# SD_Card.net
KiCad netlist of a schematic drawn in Altium Designer
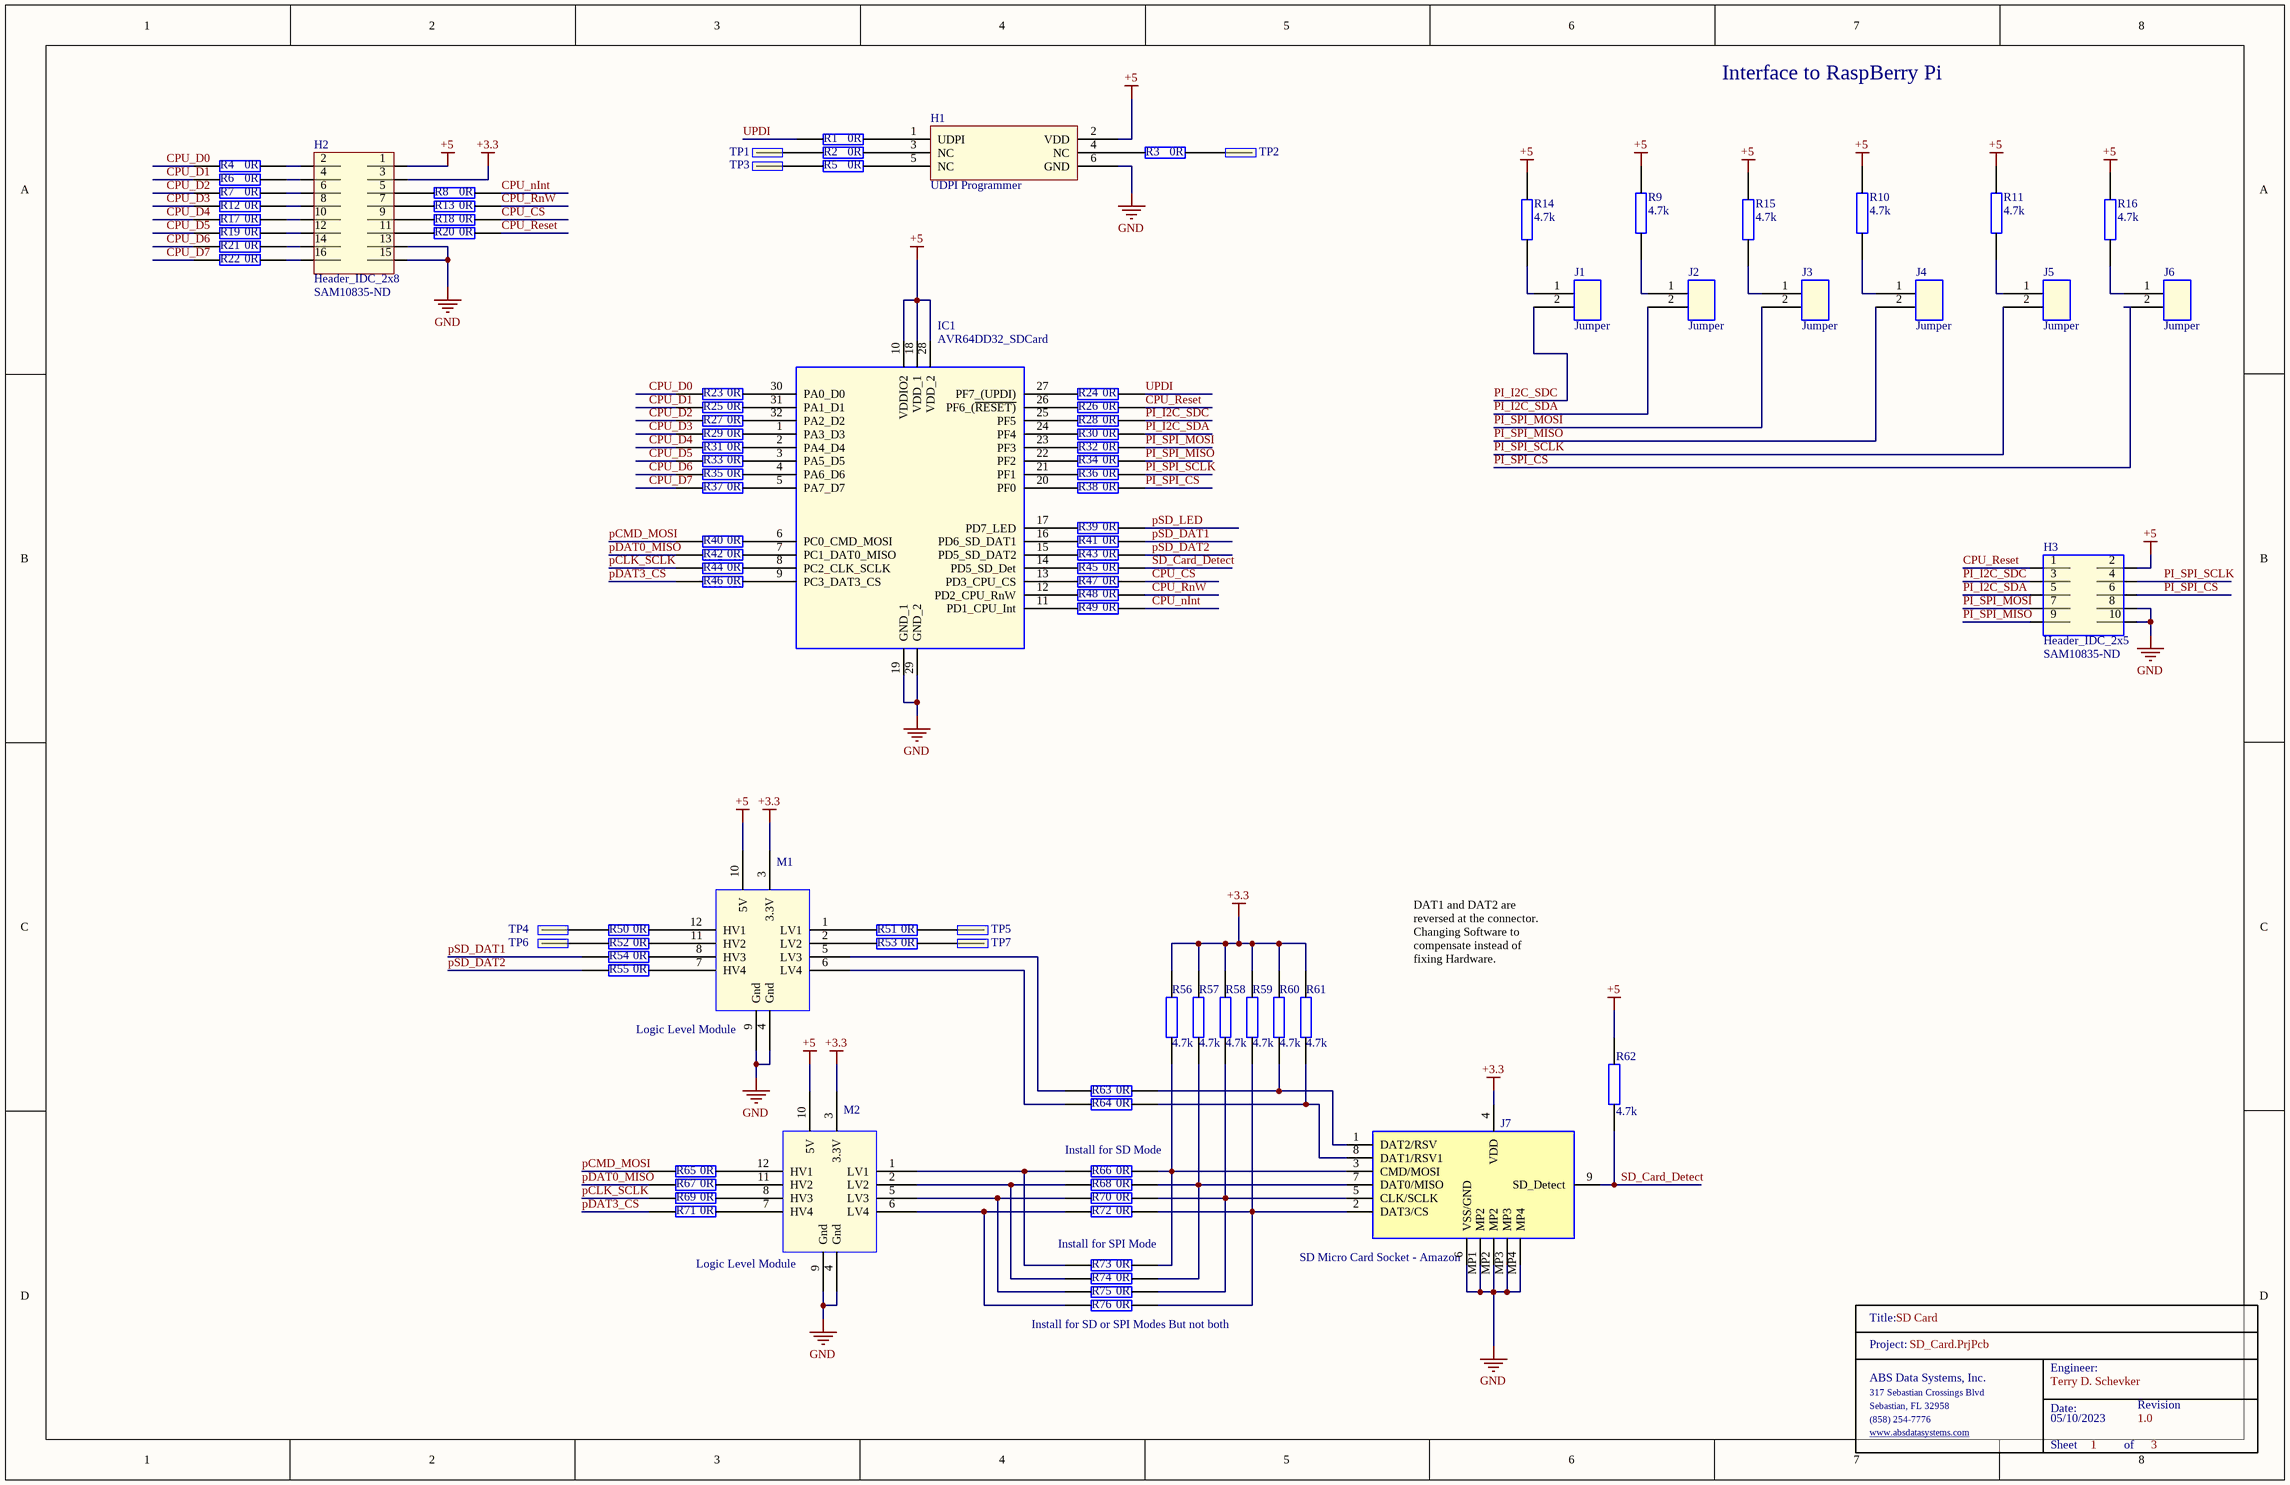
[diagram p0: SD_Card.SchDoc]

(export (version "E")
  (design (tool "Eeschema 10.0.6"))
  (components
    (comp (ref "H1")
      (value "UDPI Programmer")
      (footprint "HDR2X3")
      (description "6 Pin 2X3 Through Hole Header")
      (libsource (lib "Misc") (part "UDPI Programmer"))
    )
    (comp (ref "H2")
      (value "Header_IDC_2x8")
      (footprint "HEADER16")
      (description "16 Pin 2x8 Through Hold IDC Connector")
      (fields
        (field (name "MANUFACTURER") "Samtec")
        (field (name "MANUFACTURER PART NUMBER") "TST-108-01-G-D")
        (field (name "SUPPLIER PART NUMBER 1") "SAM10835-ND")
      )
      (libsource (lib "Misc") (part "Header_IDC_2x8"))
    )
    (comp (ref "H3")
      (value "Header_IDC_2x5")
      (footprint "HDR2X5")
      (description "10 Pin 2x5 Through Hold IDC Connector")
      (fields
        (field (name "MANUFACTURER") "Samtec")
        (field (name "MANUFACTURER PART NUMBER") "TST-105-01-G-D")
        (field (name "SUPPLIER PART NUMBER 1") "SAM10835-ND")
      )
      (libsource (lib "Misc") (part "Header_IDC_2x5"))
    )
    (comp (ref "IC1")
      (value "AVR64DD32_SDCard")
      (footprint "QFP80P900X900X120-32N")
      (description "Integrated Circuit")
      (fields (field (name "MANUFACTURER_PART_NUMBER") "AVR64DD32-I/PT ¦ MULTI-VOLTAGE I/O"))
      (libsource (lib "CPU_Memory") (part "AVR64DD32_SDCard"))
    )
    (comp (ref "J1")
      (value "Jumper")
      (footprint "Jumper")
      (description "16 Pin 3x8 Through Hold Jumprts")
      (fields
        (field (name "MANUFACTURER") "Samtec")
        (field (name "MANUFACTURER PART NUMBER") "TST-108-01-G-D")
      )
      (libsource (lib "Misc") (part "Jumper"))
    )
    (comp (ref "J2")
      (value "Jumper")
      (footprint "Jumper")
      (description "16 Pin 3x8 Through Hold Jumprts")
      (fields
        (field (name "MANUFACTURER") "Samtec")
        (field (name "MANUFACTURER PART NUMBER") "TST-108-01-G-D")
      )
      (libsource (lib "Misc") (part "Jumper"))
    )
    (comp (ref "J3")
      (value "Jumper")
      (footprint "Jumper")
      (description "16 Pin 3x8 Through Hold Jumprts")
      (fields
        (field (name "MANUFACTURER") "Samtec")
        (field (name "MANUFACTURER PART NUMBER") "TST-108-01-G-D")
      )
      (libsource (lib "Misc") (part "Jumper"))
    )
    (comp (ref "J4")
      (value "Jumper")
      (footprint "Jumper")
      (description "16 Pin 3x8 Through Hold Jumprts")
      (fields
        (field (name "MANUFACTURER") "Samtec")
        (field (name "MANUFACTURER PART NUMBER") "TST-108-01-G-D")
      )
      (libsource (lib "Misc") (part "Jumper"))
    )
    (comp (ref "J5")
      (value "Jumper")
      (footprint "Jumper")
      (description "16 Pin 3x8 Through Hold Jumprts")
      (fields
        (field (name "MANUFACTURER") "Samtec")
        (field (name "MANUFACTURER PART NUMBER") "TST-108-01-G-D")
      )
      (libsource (lib "Misc") (part "Jumper"))
    )
    (comp (ref "J6")
      (value "Jumper")
      (footprint "Jumper")
      (description "16 Pin 3x8 Through Hold Jumprts")
      (fields
        (field (name "MANUFACTURER") "Samtec")
        (field (name "MANUFACTURER PART NUMBER") "TST-108-01-G-D")
      )
      (libsource (lib "Misc") (part "Jumper"))
    )
    (comp (ref "J7")
      (value "SD Micro Card Socket - Amazon")
      (footprint "SDMicroConnector")
      (description "Memory Card Connectors 9P R/A SMT MICRO SD HINGE PUSH-PULL")
      (fields
        (field (name "MOUSER PART NUMBER") "798-DM3CSSF")
        (field (name "MANUFACTURER_PART_NUMBER") "DM3CS-SF")
      )
      (libsource (lib "Connectors") (part "SD_Micro_Socket"))
    )
    (comp (ref "M1")
      (value "Logic Level Module")
      (footprint "Logic_Level_Module")
      (description "Logic Level Converter Module")
      (libsource (lib "Logic") (part "Logic_Level_Module"))
    )
    (comp (ref "M2")
      (value "Logic Level Module")
      (footprint "Logic_Level_Module")
      (description "Logic Level Converter Module")
      (libsource (lib "Logic") (part "Logic_Level_Module"))
    )
    (comp (ref "R1")
      (value "0R")
      (footprint "0603")
      (description "YAGEO 0603 0 ohm")
      (fields
        (field (name "MOUSER PART NUMBER") "603-RC0603JR-070RL")
        (field (name "MANUFACTURER_PART_NUMBER") "RC0603JR-070RL")
      )
      (libsource (lib "Resistors") (part "RC0603JR-070RL"))
    )
    (comp (ref "R2")
      (value "0R")
      (footprint "0603")
      (description "YAGEO 0603 0 ohm")
      (fields
        (field (name "MOUSER PART NUMBER") "603-RC0603JR-070RL")
        (field (name "MANUFACTURER_PART_NUMBER") "RC0603JR-070RL")
      )
      (libsource (lib "Resistors") (part "RC0603JR-070RL"))
    )
    (comp (ref "R3")
      (value "0R")
      (footprint "0603")
      (description "YAGEO 0603 0 ohm")
      (fields
        (field (name "MOUSER PART NUMBER") "603-RC0603JR-070RL")
        (field (name "MANUFACTURER_PART_NUMBER") "RC0603JR-070RL")
      )
      (libsource (lib "Resistors") (part "RC0603JR-070RL"))
    )
    (comp (ref "R4")
      (value "0R")
      (footprint "0603")
      (description "YAGEO 0603 0 ohm")
      (fields
        (field (name "MOUSER PART NUMBER") "603-RC0603JR-070RL")
        (field (name "MANUFACTURER_PART_NUMBER") "RC0603JR-070RL")
      )
      (libsource (lib "Resistors") (part "RC0603JR-070RL"))
    )
    (comp (ref "R5")
      (value "0R")
      (footprint "0603")
      (description "YAGEO 0603 0 ohm")
      (fields
        (field (name "MOUSER PART NUMBER") "603-RC0603JR-070RL")
        (field (name "MANUFACTURER_PART_NUMBER") "RC0603JR-070RL")
      )
      (libsource (lib "Resistors") (part "RC0603JR-070RL"))
    )
    (comp (ref "R6")
      (value "0R")
      (footprint "0603")
      (description "YAGEO 0603 0 ohm")
      (fields
        (field (name "MOUSER PART NUMBER") "603-RC0603JR-070RL")
        (field (name "MANUFACTURER_PART_NUMBER") "RC0603JR-070RL")
      )
      (libsource (lib "Resistors") (part "RC0603JR-070RL"))
    )
    (comp (ref "R7")
      (value "0R")
      (footprint "0603")
      (description "YAGEO 0603 0 ohm")
      (fields
        (field (name "MOUSER PART NUMBER") "603-RC0603JR-070RL")
        (field (name "MANUFACTURER_PART_NUMBER") "RC0603JR-070RL")
      )
      (libsource (lib "Resistors") (part "RC0603JR-070RL"))
    )
    (comp (ref "R8")
      (value "0R")
      (footprint "0603")
      (description "YAGEO 0603 0 ohm")
      (fields
        (field (name "MOUSER PART NUMBER") "603-RC0603JR-070RL")
        (field (name "MANUFACTURER_PART_NUMBER") "RC0603JR-070RL")
      )
      (libsource (lib "Resistors") (part "RC0603JR-070RL"))
    )
    (comp (ref "R9")
      (value "4.7k")
      (footprint "0603")
      (description "YAGEO 0603 4.7k")
      (fields
        (field (name "MOUSER PART NUMBER") "603-RC0603JR-070RL")
        (field (name "MANUFACTURER_PART_NUMBER") "RC0603JR-070RL")
      )
      (libsource (lib "Resistors") (part "RC0603FR-104K7L"))
    )
    (comp (ref "R10")
      (value "4.7k")
      (footprint "0603")
      (description "YAGEO 0603 4.7k")
      (fields
        (field (name "MOUSER PART NUMBER") "603-RC0603JR-070RL")
        (field (name "MANUFACTURER_PART_NUMBER") "RC0603JR-070RL")
      )
      (libsource (lib "Resistors") (part "RC0603FR-104K7L"))
    )
    (comp (ref "R11")
      (value "4.7k")
      (footprint "0603")
      (description "YAGEO 0603 4.7k")
      (fields
        (field (name "MOUSER PART NUMBER") "603-RC0603JR-070RL")
        (field (name "MANUFACTURER_PART_NUMBER") "RC0603JR-070RL")
      )
      (libsource (lib "Resistors") (part "RC0603FR-104K7L"))
    )
    (comp (ref "R12")
      (value "0R")
      (footprint "0603")
      (description "YAGEO 0603 0 ohm")
      (fields
        (field (name "MOUSER PART NUMBER") "603-RC0603JR-070RL")
        (field (name "MANUFACTURER_PART_NUMBER") "RC0603JR-070RL")
      )
      (libsource (lib "Resistors") (part "RC0603JR-070RL"))
    )
    (comp (ref "R13")
      (value "0R")
      (footprint "0603")
      (description "YAGEO 0603 0 ohm")
      (fields
        (field (name "MOUSER PART NUMBER") "603-RC0603JR-070RL")
        (field (name "MANUFACTURER_PART_NUMBER") "RC0603JR-070RL")
      )
      (libsource (lib "Resistors") (part "RC0603JR-070RL"))
    )
    (comp (ref "R14")
      (value "4.7k")
      (footprint "0603")
      (description "YAGEO 0603 4.7k")
      (fields
        (field (name "MOUSER PART NUMBER") "603-RC0603JR-070RL")
        (field (name "MANUFACTURER_PART_NUMBER") "RC0603JR-070RL")
      )
      (libsource (lib "Resistors") (part "RC0603FR-104K7L"))
    )
    (comp (ref "R15")
      (value "4.7k")
      (footprint "0603")
      (description "YAGEO 0603 4.7k")
      (fields
        (field (name "MOUSER PART NUMBER") "603-RC0603JR-070RL")
        (field (name "MANUFACTURER_PART_NUMBER") "RC0603JR-070RL")
      )
      (libsource (lib "Resistors") (part "RC0603FR-104K7L"))
    )
    (comp (ref "R16")
      (value "4.7k")
      (footprint "0603")
      (description "YAGEO 0603 4.7k")
      (fields
        (field (name "MOUSER PART NUMBER") "603-RC0603JR-070RL")
        (field (name "MANUFACTURER_PART_NUMBER") "RC0603JR-070RL")
      )
      (libsource (lib "Resistors") (part "RC0603FR-104K7L"))
    )
    (comp (ref "R17")
      (value "0R")
      (footprint "0603")
      (description "YAGEO 0603 0 ohm")
      (fields
        (field (name "MOUSER PART NUMBER") "603-RC0603JR-070RL")
        (field (name "MANUFACTURER_PART_NUMBER") "RC0603JR-070RL")
      )
      (libsource (lib "Resistors") (part "RC0603JR-070RL"))
    )
    (comp (ref "R18")
      (value "0R")
      (footprint "0603")
      (description "YAGEO 0603 0 ohm")
      (fields
        (field (name "MOUSER PART NUMBER") "603-RC0603JR-070RL")
        (field (name "MANUFACTURER_PART_NUMBER") "RC0603JR-070RL")
      )
      (libsource (lib "Resistors") (part "RC0603JR-070RL"))
    )
    (comp (ref "R19")
      (value "0R")
      (footprint "0603")
      (description "YAGEO 0603 0 ohm")
      (fields
        (field (name "MOUSER PART NUMBER") "603-RC0603JR-070RL")
        (field (name "MANUFACTURER_PART_NUMBER") "RC0603JR-070RL")
      )
      (libsource (lib "Resistors") (part "RC0603JR-070RL"))
    )
    (comp (ref "R20")
      (value "0R")
      (footprint "0603")
      (description "YAGEO 0603 0 ohm")
      (fields
        (field (name "MOUSER PART NUMBER") "603-RC0603JR-070RL")
        (field (name "MANUFACTURER_PART_NUMBER") "RC0603JR-070RL")
      )
      (libsource (lib "Resistors") (part "RC0603JR-070RL"))
    )
    (comp (ref "R21")
      (value "0R")
      (footprint "0603")
      (description "YAGEO 0603 0 ohm")
      (fields
        (field (name "MOUSER PART NUMBER") "603-RC0603JR-070RL")
        (field (name "MANUFACTURER_PART_NUMBER") "RC0603JR-070RL")
      )
      (libsource (lib "Resistors") (part "RC0603JR-070RL"))
    )
    (comp (ref "R22")
      (value "0R")
      (footprint "0603")
      (description "YAGEO 0603 0 ohm")
      (fields
        (field (name "MOUSER PART NUMBER") "603-RC0603JR-070RL")
        (field (name "MANUFACTURER_PART_NUMBER") "RC0603JR-070RL")
      )
      (libsource (lib "Resistors") (part "RC0603JR-070RL"))
    )
    (comp (ref "R23")
      (value "0R")
      (footprint "0603")
      (description "YAGEO 0603 0 ohm")
      (fields
        (field (name "MOUSER PART NUMBER") "603-RC0603JR-070RL")
        (field (name "MANUFACTURER_PART_NUMBER") "RC0603JR-070RL")
      )
      (libsource (lib "Resistors") (part "RC0603JR-070RL"))
    )
    (comp (ref "R24")
      (value "0R")
      (footprint "0603")
      (description "YAGEO 0603 0 ohm")
      (fields
        (field (name "MOUSER PART NUMBER") "603-RC0603JR-070RL")
        (field (name "MANUFACTURER_PART_NUMBER") "RC0603JR-070RL")
      )
      (libsource (lib "Resistors") (part "RC0603JR-070RL"))
    )
    (comp (ref "R25")
      (value "0R")
      (footprint "0603")
      (description "YAGEO 0603 0 ohm")
      (fields
        (field (name "MOUSER PART NUMBER") "603-RC0603JR-070RL")
        (field (name "MANUFACTURER_PART_NUMBER") "RC0603JR-070RL")
      )
      (libsource (lib "Resistors") (part "RC0603JR-070RL"))
    )
    (comp (ref "R26")
      (value "0R")
      (footprint "0603")
      (description "YAGEO 0603 0 ohm")
      (fields
        (field (name "MOUSER PART NUMBER") "603-RC0603JR-070RL")
        (field (name "MANUFACTURER_PART_NUMBER") "RC0603JR-070RL")
      )
      (libsource (lib "Resistors") (part "RC0603JR-070RL"))
    )
    (comp (ref "R27")
      (value "0R")
      (footprint "0603")
      (description "YAGEO 0603 0 ohm")
      (fields
        (field (name "MOUSER PART NUMBER") "603-RC0603JR-070RL")
        (field (name "MANUFACTURER_PART_NUMBER") "RC0603JR-070RL")
      )
      (libsource (lib "Resistors") (part "RC0603JR-070RL"))
    )
    (comp (ref "R28")
      (value "0R")
      (footprint "0603")
      (description "YAGEO 0603 0 ohm")
      (fields
        (field (name "MOUSER PART NUMBER") "603-RC0603JR-070RL")
        (field (name "MANUFACTURER_PART_NUMBER") "RC0603JR-070RL")
      )
      (libsource (lib "Resistors") (part "RC0603JR-070RL"))
    )
    (comp (ref "R29")
      (value "0R")
      (footprint "0603")
      (description "YAGEO 0603 0 ohm")
      (fields
        (field (name "MOUSER PART NUMBER") "603-RC0603JR-070RL")
        (field (name "MANUFACTURER_PART_NUMBER") "RC0603JR-070RL")
      )
      (libsource (lib "Resistors") (part "RC0603JR-070RL"))
    )
    (comp (ref "R30")
      (value "0R")
      (footprint "0603")
      (description "YAGEO 0603 0 ohm")
      (fields
        (field (name "MOUSER PART NUMBER") "603-RC0603JR-070RL")
        (field (name "MANUFACTURER_PART_NUMBER") "RC0603JR-070RL")
      )
      (libsource (lib "Resistors") (part "RC0603JR-070RL"))
    )
    (comp (ref "R31")
      (value "0R")
      (footprint "0603")
      (description "YAGEO 0603 0 ohm")
      (fields
        (field (name "MOUSER PART NUMBER") "603-RC0603JR-070RL")
        (field (name "MANUFACTURER_PART_NUMBER") "RC0603JR-070RL")
      )
      (libsource (lib "Resistors") (part "RC0603JR-070RL"))
    )
    (comp (ref "R32")
      (value "0R")
      (footprint "0603")
      (description "YAGEO 0603 0 ohm")
      (fields
        (field (name "MOUSER PART NUMBER") "603-RC0603JR-070RL")
        (field (name "MANUFACTURER_PART_NUMBER") "RC0603JR-070RL")
      )
      (libsource (lib "Resistors") (part "RC0603JR-070RL"))
    )
    (comp (ref "R33")
      (value "0R")
      (footprint "0603")
      (description "YAGEO 0603 0 ohm")
      (fields
        (field (name "MOUSER PART NUMBER") "603-RC0603JR-070RL")
        (field (name "MANUFACTURER_PART_NUMBER") "RC0603JR-070RL")
      )
      (libsource (lib "Resistors") (part "RC0603JR-070RL"))
    )
    (comp (ref "R34")
      (value "0R")
      (footprint "0603")
      (description "YAGEO 0603 0 ohm")
      (fields
        (field (name "MOUSER PART NUMBER") "603-RC0603JR-070RL")
        (field (name "MANUFACTURER_PART_NUMBER") "RC0603JR-070RL")
      )
      (libsource (lib "Resistors") (part "RC0603JR-070RL"))
    )
    (comp (ref "R35")
      (value "0R")
      (footprint "0603")
      (description "YAGEO 0603 0 ohm")
      (fields
        (field (name "MOUSER PART NUMBER") "603-RC0603JR-070RL")
        (field (name "MANUFACTURER_PART_NUMBER") "RC0603JR-070RL")
      )
      (libsource (lib "Resistors") (part "RC0603JR-070RL"))
    )
    (comp (ref "R36")
      (value "0R")
      (footprint "0603")
      (description "YAGEO 0603 0 ohm")
      (fields
        (field (name "MOUSER PART NUMBER") "603-RC0603JR-070RL")
        (field (name "MANUFACTURER_PART_NUMBER") "RC0603JR-070RL")
      )
      (libsource (lib "Resistors") (part "RC0603JR-070RL"))
    )
    (comp (ref "R37")
      (value "0R")
      (footprint "0603")
      (description "YAGEO 0603 0 ohm")
      (fields
        (field (name "MOUSER PART NUMBER") "603-RC0603JR-070RL")
        (field (name "MANUFACTURER_PART_NUMBER") "RC0603JR-070RL")
      )
      (libsource (lib "Resistors") (part "RC0603JR-070RL"))
    )
    (comp (ref "R38")
      (value "0R")
      (footprint "0603")
      (description "YAGEO 0603 0 ohm")
      (fields
        (field (name "MOUSER PART NUMBER") "603-RC0603JR-070RL")
        (field (name "MANUFACTURER_PART_NUMBER") "RC0603JR-070RL")
      )
      (libsource (lib "Resistors") (part "RC0603JR-070RL"))
    )
    (comp (ref "R39")
      (value "0R")
      (footprint "0603")
      (description "YAGEO 0603 0 ohm")
      (fields
        (field (name "MOUSER PART NUMBER") "603-RC0603JR-070RL")
        (field (name "MANUFACTURER_PART_NUMBER") "RC0603JR-070RL")
      )
      (libsource (lib "Resistors") (part "RC0603JR-070RL"))
    )
    (comp (ref "R40")
      (value "0R")
      (footprint "0603")
      (description "YAGEO 0603 0 ohm")
      (fields
        (field (name "MOUSER PART NUMBER") "603-RC0603JR-070RL")
        (field (name "MANUFACTURER_PART_NUMBER") "RC0603JR-070RL")
      )
      (libsource (lib "Resistors") (part "RC0603JR-070RL"))
    )
    (comp (ref "R41")
      (value "0R")
      (footprint "0603")
      (description "YAGEO 0603 0 ohm")
      (fields
        (field (name "MOUSER PART NUMBER") "603-RC0603JR-070RL")
        (field (name "MANUFACTURER_PART_NUMBER") "RC0603JR-070RL")
      )
      (libsource (lib "Resistors") (part "RC0603JR-070RL"))
    )
    (comp (ref "R42")
      (value "0R")
      (footprint "0603")
      (description "YAGEO 0603 0 ohm")
      (fields
        (field (name "MOUSER PART NUMBER") "603-RC0603JR-070RL")
        (field (name "MANUFACTURER_PART_NUMBER") "RC0603JR-070RL")
      )
      (libsource (lib "Resistors") (part "RC0603JR-070RL"))
    )
    (comp (ref "R43")
      (value "0R")
      (footprint "0603")
      (description "YAGEO 0603 0 ohm")
      (fields
        (field (name "MOUSER PART NUMBER") "603-RC0603JR-070RL")
        (field (name "MANUFACTURER_PART_NUMBER") "RC0603JR-070RL")
      )
      (libsource (lib "Resistors") (part "RC0603JR-070RL"))
    )
    (comp (ref "R44")
      (value "0R")
      (footprint "0603")
      (description "YAGEO 0603 0 ohm")
      (fields
        (field (name "MOUSER PART NUMBER") "603-RC0603JR-070RL")
        (field (name "MANUFACTURER_PART_NUMBER") "RC0603JR-070RL")
      )
      (libsource (lib "Resistors") (part "RC0603JR-070RL"))
    )
    (comp (ref "R45")
      (value "0R")
      (footprint "0603")
      (description "YAGEO 0603 0 ohm")
      (fields
        (field (name "MOUSER PART NUMBER") "603-RC0603JR-070RL")
        (field (name "MANUFACTURER_PART_NUMBER") "RC0603JR-070RL")
      )
      (libsource (lib "Resistors") (part "RC0603JR-070RL"))
    )
    (comp (ref "R46")
      (value "0R")
      (footprint "0603")
      (description "YAGEO 0603 0 ohm")
      (fields
        (field (name "MOUSER PART NUMBER") "603-RC0603JR-070RL")
        (field (name "MANUFACTURER_PART_NUMBER") "RC0603JR-070RL")
      )
      (libsource (lib "Resistors") (part "RC0603JR-070RL"))
    )
    (comp (ref "R47")
      (value "0R")
      (footprint "0603")
      (description "YAGEO 0603 0 ohm")
      (fields
        (field (name "MOUSER PART NUMBER") "603-RC0603JR-070RL")
        (field (name "MANUFACTURER_PART_NUMBER") "RC0603JR-070RL")
      )
      (libsource (lib "Resistors") (part "RC0603JR-070RL"))
    )
    (comp (ref "R48")
      (value "0R")
      (footprint "0603")
      (description "YAGEO 0603 0 ohm")
      (fields
        (field (name "MOUSER PART NUMBER") "603-RC0603JR-070RL")
        (field (name "MANUFACTURER_PART_NUMBER") "RC0603JR-070RL")
      )
      (libsource (lib "Resistors") (part "RC0603JR-070RL"))
    )
    (comp (ref "R49")
      (value "0R")
      (footprint "0603")
      (description "YAGEO 0603 0 ohm")
      (fields
        (field (name "MOUSER PART NUMBER") "603-RC0603JR-070RL")
        (field (name "MANUFACTURER_PART_NUMBER") "RC0603JR-070RL")
      )
      (libsource (lib "Resistors") (part "RC0603JR-070RL"))
    )
    (comp (ref "R50")
      (value "0R")
      (footprint "0603")
      (description "YAGEO 0603 0 ohm")
      (fields
        (field (name "MOUSER PART NUMBER") "603-RC0603JR-070RL")
        (field (name "MANUFACTURER_PART_NUMBER") "RC0603JR-070RL")
      )
      (libsource (lib "Resistors") (part "RC0603JR-070RL"))
    )
    (comp (ref "R51")
      (value "0R")
      (footprint "0603")
      (description "YAGEO 0603 0 ohm")
      (fields
        (field (name "MOUSER PART NUMBER") "603-RC0603JR-070RL")
        (field (name "MANUFACTURER_PART_NUMBER") "RC0603JR-070RL")
      )
      (libsource (lib "Resistors") (part "RC0603JR-070RL"))
    )
    (comp (ref "R52")
      (value "0R")
      (footprint "0603")
      (description "YAGEO 0603 0 ohm")
      (fields
        (field (name "MOUSER PART NUMBER") "603-RC0603JR-070RL")
        (field (name "MANUFACTURER_PART_NUMBER") "RC0603JR-070RL")
      )
      (libsource (lib "Resistors") (part "RC0603JR-070RL"))
    )
    (comp (ref "R53")
      (value "0R")
      (footprint "0603")
      (description "YAGEO 0603 0 ohm")
      (fields
        (field (name "MOUSER PART NUMBER") "603-RC0603JR-070RL")
        (field (name "MANUFACTURER_PART_NUMBER") "RC0603JR-070RL")
      )
      (libsource (lib "Resistors") (part "RC0603JR-070RL"))
    )
    (comp (ref "R54")
      (value "0R")
      (footprint "0603")
      (description "YAGEO 0603 0 ohm")
      (fields
        (field (name "MOUSER PART NUMBER") "603-RC0603JR-070RL")
        (field (name "MANUFACTURER_PART_NUMBER") "RC0603JR-070RL")
      )
      (libsource (lib "Resistors") (part "RC0603JR-070RL"))
    )
    (comp (ref "R55")
      (value "0R")
      (footprint "0603")
      (description "YAGEO 0603 0 ohm")
      (fields
        (field (name "MOUSER PART NUMBER") "603-RC0603JR-070RL")
        (field (name "MANUFACTURER_PART_NUMBER") "RC0603JR-070RL")
      )
      (libsource (lib "Resistors") (part "RC0603JR-070RL"))
    )
    (comp (ref "R56")
      (value "4.7k")
      (footprint "0603")
      (description "YAGEO 0603 4.7k")
      (fields
        (field (name "MOUSER PART NUMBER") "603-RC0603JR-070RL")
        (field (name "MANUFACTURER_PART_NUMBER") "RC0603JR-070RL")
      )
      (libsource (lib "Resistors") (part "RC0603FR-104K7L"))
    )
    (comp (ref "R57")
      (value "4.7k")
      (footprint "0603")
      (description "YAGEO 0603 4.7k")
      (fields
        (field (name "MOUSER PART NUMBER") "603-RC0603JR-070RL")
        (field (name "MANUFACTURER_PART_NUMBER") "RC0603JR-070RL")
      )
      (libsource (lib "Resistors") (part "RC0603FR-104K7L"))
    )
    (comp (ref "R58")
      (value "4.7k")
      (footprint "0603")
      (description "YAGEO 0603 4.7k")
      (fields
        (field (name "MOUSER PART NUMBER") "603-RC0603JR-070RL")
        (field (name "MANUFACTURER_PART_NUMBER") "RC0603JR-070RL")
      )
      (libsource (lib "Resistors") (part "RC0603FR-104K7L"))
    )
    (comp (ref "R59")
      (value "4.7k")
      (footprint "0603")
      (description "YAGEO 0603 4.7k")
      (fields
        (field (name "MOUSER PART NUMBER") "603-RC0603JR-070RL")
        (field (name "MANUFACTURER_PART_NUMBER") "RC0603JR-070RL")
      )
      (libsource (lib "Resistors") (part "RC0603FR-104K7L"))
    )
    (comp (ref "R60")
      (value "4.7k")
      (footprint "0603")
      (description "YAGEO 0603 4.7k")
      (fields
        (field (name "MOUSER PART NUMBER") "603-RC0603JR-070RL")
        (field (name "MANUFACTURER_PART_NUMBER") "RC0603JR-070RL")
      )
      (libsource (lib "Resistors") (part "RC0603FR-104K7L"))
    )
    (comp (ref "R61")
      (value "4.7k")
      (footprint "0603")
      (description "YAGEO 0603 4.7k")
      (fields
        (field (name "MOUSER PART NUMBER") "603-RC0603JR-070RL")
        (field (name "MANUFACTURER_PART_NUMBER") "RC0603JR-070RL")
      )
      (libsource (lib "Resistors") (part "RC0603FR-104K7L"))
    )
    (comp (ref "R62")
      (value "4.7k")
      (footprint "0603")
      (description "YAGEO 0603 4.7k")
      (fields
        (field (name "MOUSER PART NUMBER") "603-RC0603JR-070RL")
        (field (name "MANUFACTURER_PART_NUMBER") "RC0603JR-070RL")
      )
      (libsource (lib "Resistors") (part "RC0603FR-104K7L"))
    )
    (comp (ref "R63")
      (value "0R")
      (footprint "0603")
      (description "YAGEO 0603 0 ohm")
      (fields
        (field (name "MOUSER PART NUMBER") "603-RC0603JR-070RL")
        (field (name "MANUFACTURER_PART_NUMBER") "RC0603JR-070RL")
      )
      (libsource (lib "Resistors") (part "RC0603JR-070RL"))
    )
    (comp (ref "R64")
      (value "0R")
      (footprint "0603")
      (description "YAGEO 0603 0 ohm")
      (fields
        (field (name "MOUSER PART NUMBER") "603-RC0603JR-070RL")
        (field (name "MANUFACTURER_PART_NUMBER") "RC0603JR-070RL")
      )
      (libsource (lib "Resistors") (part "RC0603JR-070RL"))
    )
    (comp (ref "R65")
      (value "0R")
      (footprint "0603")
      (description "YAGEO 0603 0 ohm")
      (fields
        (field (name "MOUSER PART NUMBER") "603-RC0603JR-070RL")
        (field (name "MANUFACTURER_PART_NUMBER") "RC0603JR-070RL")
      )
      (libsource (lib "Resistors") (part "RC0603JR-070RL"))
    )
    (comp (ref "R66")
      (value "0R")
      (footprint "0603")
      (description "YAGEO 0603 0 ohm")
      (fields
        (field (name "MOUSER PART NUMBER") "603-RC0603JR-070RL")
        (field (name "MANUFACTURER_PART_NUMBER") "RC0603JR-070RL")
      )
      (libsource (lib "Resistors") (part "RC0603JR-070RL"))
    )
    (comp (ref "R67")
      (value "0R")
      (footprint "0603")
      (description "YAGEO 0603 0 ohm")
      (fields
        (field (name "MOUSER PART NUMBER") "603-RC0603JR-070RL")
        (field (name "MANUFACTURER_PART_NUMBER") "RC0603JR-070RL")
      )
      (libsource (lib "Resistors") (part "RC0603JR-070RL"))
    )
    (comp (ref "R68")
      (value "0R")
      (footprint "0603")
      (description "YAGEO 0603 0 ohm")
      (fields
        (field (name "MOUSER PART NUMBER") "603-RC0603JR-070RL")
        (field (name "MANUFACTURER_PART_NUMBER") "RC0603JR-070RL")
      )
      (libsource (lib "Resistors") (part "RC0603JR-070RL"))
    )
    (comp (ref "R69")
      (value "0R")
      (footprint "0603")
      (description "YAGEO 0603 0 ohm")
      (fields
        (field (name "MOUSER PART NUMBER") "603-RC0603JR-070RL")
        (field (name "MANUFACTURER_PART_NUMBER") "RC0603JR-070RL")
      )
      (libsource (lib "Resistors") (part "RC0603JR-070RL"))
    )
    (comp (ref "R70")
      (value "0R")
      (footprint "0603")
      (description "YAGEO 0603 0 ohm")
      (fields
        (field (name "MOUSER PART NUMBER") "603-RC0603JR-070RL")
        (field (name "MANUFACTURER_PART_NUMBER") "RC0603JR-070RL")
      )
      (libsource (lib "Resistors") (part "RC0603JR-070RL"))
    )
    (comp (ref "R71")
      (value "0R")
      (footprint "0603")
      (description "YAGEO 0603 0 ohm")
      (fields
        (field (name "MOUSER PART NUMBER") "603-RC0603JR-070RL")
        (field (name "MANUFACTURER_PART_NUMBER") "RC0603JR-070RL")
      )
      (libsource (lib "Resistors") (part "RC0603JR-070RL"))
    )
    (comp (ref "R72")
      (value "0R")
      (footprint "0603")
      (description "YAGEO 0603 0 ohm")
      (fields
        (field (name "MOUSER PART NUMBER") "603-RC0603JR-070RL")
        (field (name "MANUFACTURER_PART_NUMBER") "RC0603JR-070RL")
      )
      (libsource (lib "Resistors") (part "RC0603JR-070RL"))
    )
    (comp (ref "R73")
      (value "0R")
      (footprint "0603")
      (description "YAGEO 0603 0 ohm")
      (fields
        (field (name "MOUSER PART NUMBER") "603-RC0603JR-070RL")
        (field (name "MANUFACTURER_PART_NUMBER") "RC0603JR-070RL")
      )
      (libsource (lib "Resistors") (part "RC0603JR-070RL"))
    )
    (comp (ref "R74")
      (value "0R")
      (footprint "0603")
      (description "YAGEO 0603 0 ohm")
      (fields
        (field (name "MOUSER PART NUMBER") "603-RC0603JR-070RL")
        (field (name "MANUFACTURER_PART_NUMBER") "RC0603JR-070RL")
      )
      (libsource (lib "Resistors") (part "RC0603JR-070RL"))
    )
    (comp (ref "R75")
      (value "0R")
      (footprint "0603")
      (description "YAGEO 0603 0 ohm")
      (fields
        (field (name "MOUSER PART NUMBER") "603-RC0603JR-070RL")
        (field (name "MANUFACTURER_PART_NUMBER") "RC0603JR-070RL")
      )
      (libsource (lib "Resistors") (part "RC0603JR-070RL"))
    )
    (comp (ref "R76")
      (value "0R")
      (footprint "0603")
      (description "YAGEO 0603 0 ohm")
      (fields
        (field (name "MOUSER PART NUMBER") "603-RC0603JR-070RL")
        (field (name "MANUFACTURER_PART_NUMBER") "RC0603JR-070RL")
      )
      (libsource (lib "Resistors") (part "RC0603JR-070RL"))
    )
    (comp (ref "TitleBlock_1") (value "TitleBlock") (libsource (lib "Misc") (part "TitleBlock")))
    (comp (ref "TP1")
      (value "TP")
      (footprint "TP")
      (fields
        (field (name "MANUFACTURER") "Samtec")
        (field (name "MANUFACTURER PART NUMBER") "TST-105-01-G-D")
      )
      (libsource (lib "") (part "TP_1"))
    )
    (comp (ref "TP2")
      (value "TP")
      (footprint "TP")
      (fields
        (field (name "MANUFACTURER") "Samtec")
        (field (name "MANUFACTURER PART NUMBER") "TST-105-01-G-D")
      )
      (libsource (lib "Misc") (part "TP"))
    )
    (comp (ref "TP3")
      (value "TP")
      (footprint "TP")
      (fields
        (field (name "MANUFACTURER") "Samtec")
        (field (name "MANUFACTURER PART NUMBER") "TST-105-01-G-D")
      )
      (libsource (lib "") (part "TP_1"))
    )
    (comp (ref "TP4")
      (value "TP")
      (footprint "TP")
      (fields
        (field (name "MANUFACTURER") "Samtec")
        (field (name "MANUFACTURER PART NUMBER") "TST-105-01-G-D")
      )
      (libsource (lib "") (part "TP_1"))
    )
    (comp (ref "TP5")
      (value "TP")
      (footprint "TP")
      (fields
        (field (name "MANUFACTURER") "Samtec")
        (field (name "MANUFACTURER PART NUMBER") "TST-105-01-G-D")
      )
      (libsource (lib "Misc") (part "TP"))
    )
    (comp (ref "TP6")
      (value "TP")
      (footprint "TP")
      (fields
        (field (name "MANUFACTURER") "Samtec")
        (field (name "MANUFACTURER PART NUMBER") "TST-105-01-G-D")
      )
      (libsource (lib "") (part "TP_1"))
    )
    (comp (ref "TP7")
      (value "TP")
      (footprint "TP")
      (fields
        (field (name "MANUFACTURER") "Samtec")
        (field (name "MANUFACTURER PART NUMBER") "TST-105-01-G-D")
      )
      (libsource (lib "Misc") (part "TP"))
    )
  )
  (nets
    (net (code "1") (name "+3.3") (class "Default")
      (node (ref "H2") (pin "3") (pinfunction "3_3") (pintype "passive"))
      (node (ref "J7") (pin "4") (pinfunction "VDD_4") (pintype "passive"))
      (node (ref "M1") (pin "3") (pinfunction "3.3V_3") (pintype "passive"))
      (node (ref "M2") (pin "3") (pinfunction "3.3V_3") (pintype "passive"))
      (node (ref "R56") (pin "2") (pinfunction "2_2") (pintype "passive"))
      (node (ref "R57") (pin "2") (pinfunction "2_2") (pintype "passive"))
      (node (ref "R58") (pin "2") (pinfunction "2_2") (pintype "passive"))
      (node (ref "R59") (pin "2") (pinfunction "2_2") (pintype "passive"))
      (node (ref "R60") (pin "2") (pinfunction "2_2") (pintype "passive"))
      (node (ref "R61") (pin "2") (pinfunction "2_2") (pintype "passive"))
    )
    (net (code "2") (name "+5") (class "Default")
      (node (ref "H1") (pin "2") (pinfunction "VDD_2") (pintype "passive"))
      (node (ref "H2") (pin "1") (pinfunction "1_1") (pintype "passive"))
      (node (ref "H3") (pin "2") (pinfunction "2_2") (pintype "passive"))
      (node (ref "IC1") (pin "10") (pinfunction "VDDIO2_10") (pintype "passive"))
      (node (ref "IC1") (pin "18") (pinfunction "VDD_1_18") (pintype "passive"))
      (node (ref "IC1") (pin "28") (pinfunction "VDD_2_28") (pintype "passive"))
      (node (ref "M1") (pin "10") (pinfunction "5V_10") (pintype "passive"))
      (node (ref "M2") (pin "10") (pinfunction "5V_10") (pintype "passive"))
      (node (ref "R10") (pin "2") (pinfunction "2_2") (pintype "passive"))
      (node (ref "R11") (pin "2") (pinfunction "2_2") (pintype "passive"))
      (node (ref "R14") (pin "2") (pinfunction "2_2") (pintype "passive"))
      (node (ref "R15") (pin "2") (pinfunction "2_2") (pintype "passive"))
      (node (ref "R16") (pin "1") (pinfunction "1_1") (pintype "passive"))
      (node (ref "R62") (pin "2") (pinfunction "2_2") (pintype "passive"))
      (node (ref "R9") (pin "2") (pinfunction "2_2") (pintype "passive"))
    )
    (net (code "3") (name "/CPU_CS") (class "Default")
      (node (ref "R18") (pin "2") (pinfunction "2_2") (pintype "passive"))
      (node (ref "R47") (pin "2") (pinfunction "2_2") (pintype "passive"))
    )
    (net (code "4") (name "/CPU_D0") (class "Default")
      (node (ref "R23") (pin "1") (pinfunction "1_1") (pintype "passive"))
      (node (ref "R4") (pin "1") (pinfunction "1_1") (pintype "passive"))
    )
    (net (code "5") (name "/CPU_D1") (class "Default")
      (node (ref "R25") (pin "1") (pinfunction "1_1") (pintype "passive"))
      (node (ref "R6") (pin "1") (pinfunction "1_1") (pintype "passive"))
    )
    (net (code "6") (name "/CPU_D2") (class "Default")
      (node (ref "R27") (pin "1") (pinfunction "1_1") (pintype "passive"))
      (node (ref "R7") (pin "1") (pinfunction "1_1") (pintype "passive"))
    )
    (net (code "7") (name "/CPU_D3") (class "Default")
      (node (ref "R12") (pin "1") (pinfunction "1_1") (pintype "passive"))
      (node (ref "R29") (pin "1") (pinfunction "1_1") (pintype "passive"))
    )
    (net (code "8") (name "/CPU_D4") (class "Default")
      (node (ref "R17") (pin "1") (pinfunction "1_1") (pintype "passive"))
      (node (ref "R31") (pin "1") (pinfunction "1_1") (pintype "passive"))
    )
    (net (code "9") (name "/CPU_D5") (class "Default")
      (node (ref "R19") (pin "1") (pinfunction "1_1") (pintype "passive"))
      (node (ref "R33") (pin "1") (pinfunction "1_1") (pintype "passive"))
    )
    (net (code "10") (name "/CPU_D6") (class "Default")
      (node (ref "R21") (pin "1") (pinfunction "1_1") (pintype "passive"))
      (node (ref "R35") (pin "1") (pinfunction "1_1") (pintype "passive"))
    )
    (net (code "11") (name "/CPU_D7") (class "Default")
      (node (ref "R22") (pin "1") (pinfunction "1_1") (pintype "passive"))
      (node (ref "R37") (pin "1") (pinfunction "1_1") (pintype "passive"))
    )
    (net (code "12") (name "/CPU_Reset") (class "Default")
      (node (ref "H3") (pin "1") (pinfunction "1_1") (pintype "passive"))
      (node (ref "R20") (pin "2") (pinfunction "2_2") (pintype "passive"))
      (node (ref "R26") (pin "2") (pinfunction "2_2") (pintype "passive"))
    )
    (net (code "13") (name "/CPU_RnW") (class "Default")
      (node (ref "R13") (pin "2") (pinfunction "2_2") (pintype "passive"))
      (node (ref "R48") (pin "2") (pinfunction "2_2") (pintype "passive"))
    )
    (net (code "14") (name "/CPU_nInt") (class "Default")
      (node (ref "R49") (pin "2") (pinfunction "2_2") (pintype "passive"))
      (node (ref "R8") (pin "2") (pinfunction "2_2") (pintype "passive"))
    )
    (net (code "15") (name "/PI_I2C_SDA") (class "Default")
      (node (ref "H3") (pin "5") (pinfunction "5_5") (pintype "passive"))
      (node (ref "J2") (pin "2") (pinfunction "2_2") (pintype "passive"))
      (node (ref "R30") (pin "2") (pinfunction "2_2") (pintype "passive"))
    )
    (net (code "16") (name "/PI_I2C_SDC") (class "Default")
      (node (ref "H3") (pin "3") (pinfunction "3_3") (pintype "passive"))
      (node (ref "J1") (pin "2") (pinfunction "2_2") (pintype "passive"))
      (node (ref "R28") (pin "2") (pinfunction "2_2") (pintype "passive"))
    )
    (net (code "17") (name "/PI_SPI_CS") (class "Default")
      (node (ref "H3") (pin "6") (pinfunction "6_6") (pintype "passive"))
      (node (ref "J6") (pin "2") (pinfunction "2_2") (pintype "passive"))
      (node (ref "R38") (pin "2") (pinfunction "2_2") (pintype "passive"))
    )
    (net (code "18") (name "/PI_SPI_MISO") (class "Default")
      (node (ref "H3") (pin "9") (pinfunction "9_9") (pintype "passive"))
      (node (ref "J4") (pin "2") (pinfunction "2_2") (pintype "passive"))
      (node (ref "R34") (pin "2") (pinfunction "2_2") (pintype "passive"))
    )
    (net (code "19") (name "/PI_SPI_MOSI") (class "Default")
      (node (ref "H3") (pin "7") (pinfunction "7_7") (pintype "passive"))
      (node (ref "J3") (pin "2") (pinfunction "2_2") (pintype "passive"))
      (node (ref "R32") (pin "2") (pinfunction "2_2") (pintype "passive"))
    )
    (net (code "20") (name "/PI_SPI_SCLK") (class "Default")
      (node (ref "H3") (pin "4") (pinfunction "4_4") (pintype "passive"))
      (node (ref "J5") (pin "2") (pinfunction "2_2") (pintype "passive"))
      (node (ref "R36") (pin "2") (pinfunction "2_2") (pintype "passive"))
    )
    (net (code "21") (name "/SD_Card_Detect") (class "Default")
      (node (ref "J7") (pin "9") (pinfunction "SD_Detect_9") (pintype "passive"))
      (node (ref "R45") (pin "2") (pinfunction "2_2") (pintype "passive"))
      (node (ref "R62") (pin "1") (pinfunction "1_1") (pintype "passive"))
    )
    (net (code "22") (name "/UPDI") (class "Default")
      (node (ref "R1") (pin "1") (pinfunction "1_1") (pintype "passive"))
      (node (ref "R24") (pin "2") (pinfunction "2_2") (pintype "passive"))
    )
    (net (code "23") (name "/pCLK_SCLK") (class "Default")
      (node (ref "R44") (pin "1") (pinfunction "1_1") (pintype "passive"))
      (node (ref "R69") (pin "1") (pinfunction "1_1") (pintype "passive"))
    )
    (net (code "24") (name "/pCMD_MOSI") (class "Default")
      (node (ref "R40") (pin "1") (pinfunction "1_1") (pintype "passive"))
      (node (ref "R65") (pin "1") (pinfunction "1_1") (pintype "passive"))
    )
    (net (code "25") (name "/pDAT0_MISO") (class "Default")
      (node (ref "R42") (pin "1") (pinfunction "1_1") (pintype "passive"))
      (node (ref "R67") (pin "1") (pinfunction "1_1") (pintype "passive"))
    )
    (net (code "26") (name "/pDAT3_CS") (class "Default")
      (node (ref "R46") (pin "1") (pinfunction "1_1") (pintype "passive"))
      (node (ref "R71") (pin "1") (pinfunction "1_1") (pintype "passive"))
    )
    (net (code "27") (name "/pSD_DAT1") (class "Default")
      (node (ref "R41") (pin "2") (pinfunction "2_2") (pintype "passive"))
      (node (ref "R54") (pin "1") (pinfunction "1_1") (pintype "passive"))
    )
    (net (code "28") (name "/pSD_DAT2") (class "Default")
      (node (ref "R43") (pin "2") (pinfunction "2_2") (pintype "passive"))
      (node (ref "R55") (pin "1") (pinfunction "1_1") (pintype "passive"))
    )
    (net (code "29") (name "/pSD_LED") (class "Default")
      (node (ref "R39") (pin "2") (pinfunction "2_2") (pintype "passive"))
    )
    (net (code "30") (name "GND") (class "Default")
      (node (ref "H1") (pin "6") (pinfunction "GND_6") (pintype "passive"))
      (node (ref "H2") (pin "13") (pinfunction "13_13") (pintype "passive"))
      (node (ref "H2") (pin "15") (pinfunction "15_15") (pintype "passive"))
      (node (ref "H3") (pin "10") (pinfunction "10_10") (pintype "passive"))
      (node (ref "H3") (pin "8") (pinfunction "8_8") (pintype "passive"))
      (node (ref "IC1") (pin "19") (pinfunction "GND_1_19") (pintype "passive"))
      (node (ref "IC1") (pin "29") (pinfunction "GND_2_29") (pintype "passive"))
      (node (ref "J7") (pin "6") (pinfunction "VSS/GND_6") (pintype "passive"))
      (node (ref "J7") (pin "MP1") (pinfunction "MP2_MP1") (pintype "passive"))
      (node (ref "J7") (pin "MP2") (pinfunction "MP2_MP2") (pintype "passive"))
      (node (ref "J7") (pin "MP3") (pinfunction "MP3_MP3") (pintype "passive"))
      (node (ref "J7") (pin "MP4") (pinfunction "MP4_MP4") (pintype "passive"))
      (node (ref "M1") (pin "4") (pinfunction "Gnd_4") (pintype "passive"))
      (node (ref "M1") (pin "9") (pinfunction "Gnd_9") (pintype "passive"))
      (node (ref "M2") (pin "4") (pinfunction "Gnd_4") (pintype "passive"))
      (node (ref "M2") (pin "9") (pinfunction "Gnd_9") (pintype "passive"))
    )
    (net (code "31") (name "Net-(H1-NC-Pad3)") (class "Default")
      (node (ref "H1") (pin "3") (pinfunction "NC_3") (pintype "passive"))
      (node (ref "R2") (pin "2") (pinfunction "2_2") (pintype "passive"))
    )
    (net (code "32") (name "Net-(H1-NC-Pad4)") (class "Default")
      (node (ref "H1") (pin "4") (pinfunction "NC_4") (pintype "passive"))
      (node (ref "R3") (pin "1") (pinfunction "1_1") (pintype "passive"))
    )
    (net (code "33") (name "Net-(H1-NC-Pad5)") (class "Default")
      (node (ref "H1") (pin "5") (pinfunction "NC_5") (pintype "passive"))
      (node (ref "R5") (pin "2") (pinfunction "2_2") (pintype "passive"))
    )
    (net (code "34") (name "Net-(H1-UDPI)") (class "Default")
      (node (ref "H1") (pin "1") (pinfunction "UDPI_1") (pintype "passive"))
      (node (ref "R1") (pin "2") (pinfunction "2_2") (pintype "passive"))
    )
    (net (code "35") (name "Net-(H2-Pad2)") (class "Default")
      (node (ref "H2") (pin "2") (pinfunction "2_2") (pintype "passive"))
      (node (ref "R4") (pin "2") (pinfunction "2_2") (pintype "passive"))
    )
    (net (code "36") (name "Net-(H2-Pad4)") (class "Default")
      (node (ref "H2") (pin "4") (pinfunction "4_4") (pintype "passive"))
      (node (ref "R6") (pin "2") (pinfunction "2_2") (pintype "passive"))
    )
    (net (code "37") (name "Net-(H2-Pad5)") (class "Default")
      (node (ref "H2") (pin "5") (pinfunction "5_5") (pintype "passive"))
      (node (ref "R8") (pin "1") (pinfunction "1_1") (pintype "passive"))
    )
    (net (code "38") (name "Net-(H2-Pad6)") (class "Default")
      (node (ref "H2") (pin "6") (pinfunction "6_6") (pintype "passive"))
      (node (ref "R7") (pin "2") (pinfunction "2_2") (pintype "passive"))
    )
    (net (code "39") (name "Net-(H2-Pad7)") (class "Default")
      (node (ref "H2") (pin "7") (pinfunction "7_7") (pintype "passive"))
      (node (ref "R13") (pin "1") (pinfunction "1_1") (pintype "passive"))
    )
    (net (code "40") (name "Net-(H2-Pad8)") (class "Default")
      (node (ref "H2") (pin "8") (pinfunction "8_8") (pintype "passive"))
      (node (ref "R12") (pin "2") (pinfunction "2_2") (pintype "passive"))
    )
    (net (code "41") (name "Net-(H2-Pad9)") (class "Default")
      (node (ref "H2") (pin "9") (pinfunction "9_9") (pintype "passive"))
      (node (ref "R18") (pin "1") (pinfunction "1_1") (pintype "passive"))
    )
    (net (code "42") (name "Net-(H2-Pad10)") (class "Default")
      (node (ref "H2") (pin "10") (pinfunction "10_10") (pintype "passive"))
      (node (ref "R17") (pin "2") (pinfunction "2_2") (pintype "passive"))
    )
    (net (code "43") (name "Net-(H2-Pad11)") (class "Default")
      (node (ref "H2") (pin "11") (pinfunction "11_11") (pintype "passive"))
      (node (ref "R20") (pin "1") (pinfunction "1_1") (pintype "passive"))
    )
    (net (code "44") (name "Net-(H2-Pad12)") (class "Default")
      (node (ref "H2") (pin "12") (pinfunction "12_12") (pintype "passive"))
      (node (ref "R19") (pin "2") (pinfunction "2_2") (pintype "passive"))
    )
    (net (code "45") (name "Net-(H2-Pad14)") (class "Default")
      (node (ref "H2") (pin "14") (pinfunction "14_14") (pintype "passive"))
      (node (ref "R21") (pin "2") (pinfunction "2_2") (pintype "passive"))
    )
    (net (code "46") (name "Net-(H2-Pad16)") (class "Default")
      (node (ref "H2") (pin "16") (pinfunction "16_16") (pintype "passive"))
      (node (ref "R22") (pin "2") (pinfunction "2_2") (pintype "passive"))
    )
    (net (code "47") (name "Net-(IC1-PA0_D0)") (class "Default")
      (node (ref "IC1") (pin "30") (pinfunction "PA0_D0_30") (pintype "passive"))
      (node (ref "R23") (pin "2") (pinfunction "2_2") (pintype "passive"))
    )
    (net (code "48") (name "Net-(IC1-PA1_D1)") (class "Default")
      (node (ref "IC1") (pin "31") (pinfunction "PA1_D1_31") (pintype "passive"))
      (node (ref "R25") (pin "2") (pinfunction "2_2") (pintype "passive"))
    )
    (net (code "49") (name "Net-(IC1-PA2_D2)") (class "Default")
      (node (ref "IC1") (pin "32") (pinfunction "PA2_D2_32") (pintype "passive"))
      (node (ref "R27") (pin "2") (pinfunction "2_2") (pintype "passive"))
    )
    (net (code "50") (name "Net-(IC1-PA3_D3)") (class "Default")
      (node (ref "IC1") (pin "1") (pinfunction "PA3_D3_1") (pintype "passive"))
      (node (ref "R29") (pin "2") (pinfunction "2_2") (pintype "passive"))
    )
    (net (code "51") (name "Net-(IC1-PA4_D4)") (class "Default")
      (node (ref "IC1") (pin "2") (pinfunction "PA4_D4_2") (pintype "passive"))
      (node (ref "R31") (pin "2") (pinfunction "2_2") (pintype "passive"))
    )
    (net (code "52") (name "Net-(IC1-PA5_D5)") (class "Default")
      (node (ref "IC1") (pin "3") (pinfunction "PA5_D5_3") (pintype "passive"))
      (node (ref "R33") (pin "2") (pinfunction "2_2") (pintype "passive"))
    )
    (net (code "53") (name "Net-(IC1-PA6_D6)") (class "Default")
      (node (ref "IC1") (pin "4") (pinfunction "PA6_D6_4") (pintype "passive"))
      (node (ref "R35") (pin "2") (pinfunction "2_2") (pintype "passive"))
    )
    (net (code "54") (name "Net-(IC1-PA7_D7)") (class "Default")
      (node (ref "IC1") (pin "5") (pinfunction "PA7_D7_5") (pintype "passive"))
      (node (ref "R37") (pin "2") (pinfunction "2_2") (pintype "passive"))
    )
    (net (code "55") (name "Net-(IC1-PC0_CMD_MOSI)") (class "Default")
      (node (ref "IC1") (pin "6") (pinfunction "PC0_CMD_MOSI_6") (pintype "passive"))
      (node (ref "R40") (pin "2") (pinfunction "2_2") (pintype "passive"))
    )
    (net (code "56") (name "Net-(IC1-PC1_DAT0_MISO)") (class "Default")
      (node (ref "IC1") (pin "7") (pinfunction "PC1_DAT0_MISO_7") (pintype "passive"))
      (node (ref "R42") (pin "2") (pinfunction "2_2") (pintype "passive"))
    )
    (net (code "57") (name "Net-(IC1-PC2_CLK_SCLK)") (class "Default")
      (node (ref "IC1") (pin "8") (pinfunction "PC2_CLK_SCLK_8") (pintype "passive"))
      (node (ref "R44") (pin "2") (pinfunction "2_2") (pintype "passive"))
    )
    (net (code "58") (name "Net-(IC1-PC3_DAT3_CS)") (class "Default")
      (node (ref "IC1") (pin "9") (pinfunction "PC3_DAT3_CS_9") (pintype "passive"))
      (node (ref "R46") (pin "2") (pinfunction "2_2") (pintype "passive"))
    )
    (net (code "59") (name "Net-(IC1-PD1_CPU_Int)") (class "Default")
      (node (ref "IC1") (pin "11") (pinfunction "PD1_CPU_Int_11") (pintype "passive"))
      (node (ref "R49") (pin "1") (pinfunction "1_1") (pintype "passive"))
    )
    (net (code "60") (name "Net-(IC1-PD2_CPU_RnW)") (class "Default")
      (node (ref "IC1") (pin "12") (pinfunction "PD2_CPU_RnW_12") (pintype "passive"))
      (node (ref "R48") (pin "1") (pinfunction "1_1") (pintype "passive"))
    )
    (net (code "61") (name "Net-(IC1-PD3_CPU_CS)") (class "Default")
      (node (ref "IC1") (pin "13") (pinfunction "PD3_CPU_CS_13") (pintype "passive"))
      (node (ref "R47") (pin "1") (pinfunction "1_1") (pintype "passive"))
    )
    (net (code "62") (name "Net-(IC1-PD5_SD_DAT2)") (class "Default")
      (node (ref "IC1") (pin "15") (pinfunction "PD5_SD_DAT2_15") (pintype "passive"))
      (node (ref "R43") (pin "1") (pinfunction "1_1") (pintype "passive"))
    )
    (net (code "63") (name "Net-(IC1-PD5_SD_Det)") (class "Default")
      (node (ref "IC1") (pin "14") (pinfunction "PD5_SD_Det_14") (pintype "passive"))
      (node (ref "R45") (pin "1") (pinfunction "1_1") (pintype "passive"))
    )
    (net (code "64") (name "Net-(IC1-PD6_SD_DAT1)") (class "Default")
      (node (ref "IC1") (pin "16") (pinfunction "PD6_SD_DAT1_16") (pintype "passive"))
      (node (ref "R41") (pin "1") (pinfunction "1_1") (pintype "passive"))
    )
    (net (code "65") (name "Net-(IC1-PD7_LED)") (class "Default")
      (node (ref "IC1") (pin "17") (pinfunction "PD7_LED_17") (pintype "passive"))
      (node (ref "R39") (pin "1") (pinfunction "1_1") (pintype "passive"))
    )
    (net (code "66") (name "Net-(IC1-PF0)") (class "Default")
      (node (ref "IC1") (pin "20") (pinfunction "PF0_20") (pintype "passive"))
      (node (ref "R38") (pin "1") (pinfunction "1_1") (pintype "passive"))
    )
    (net (code "67") (name "Net-(IC1-PF1)") (class "Default")
      (node (ref "IC1") (pin "21") (pinfunction "PF1_21") (pintype "passive"))
      (node (ref "R36") (pin "1") (pinfunction "1_1") (pintype "passive"))
    )
    (net (code "68") (name "Net-(IC1-PF2)") (class "Default")
      (node (ref "IC1") (pin "22") (pinfunction "PF2_22") (pintype "passive"))
      (node (ref "R34") (pin "1") (pinfunction "1_1") (pintype "passive"))
    )
    (net (code "69") (name "Net-(IC1-PF3)") (class "Default")
      (node (ref "IC1") (pin "23") (pinfunction "PF3_23") (pintype "passive"))
      (node (ref "R32") (pin "1") (pinfunction "1_1") (pintype "passive"))
    )
    (net (code "70") (name "Net-(IC1-PF4)") (class "Default")
      (node (ref "IC1") (pin "24") (pinfunction "PF4_24") (pintype "passive"))
      (node (ref "R30") (pin "1") (pinfunction "1_1") (pintype "passive"))
    )
    (net (code "71") (name "Net-(IC1-PF5)") (class "Default")
      (node (ref "IC1") (pin "25") (pinfunction "PF5_25") (pintype "passive"))
      (node (ref "R28") (pin "1") (pinfunction "1_1") (pintype "passive"))
    )
    (net (code "72") (name "Net-(IC1-PF6_(~{RESET)})") (class "Default")
      (node (ref "IC1") (pin "26") (pinfunction "PF6_(~{RESET)}_26") (pintype "passive"))
      (node (ref "R26") (pin "1") (pinfunction "1_1") (pintype "passive"))
    )
    (net (code "73") (name "Net-(IC1-PF7_(UPDI))") (class "Default")
      (node (ref "IC1") (pin "27") (pinfunction "PF7_(UPDI)_27") (pintype "passive"))
      (node (ref "R24") (pin "1") (pinfunction "1_1") (pintype "passive"))
    )
    (net (code "74") (name "Net-(J1-Pad1)") (class "Default")
      (node (ref "J1") (pin "1") (pinfunction "1_1") (pintype "passive"))
      (node (ref "R14") (pin "1") (pinfunction "1_1") (pintype "passive"))
    )
    (net (code "75") (name "Net-(J2-Pad1)") (class "Default")
      (node (ref "J2") (pin "1") (pinfunction "1_1") (pintype "passive"))
      (node (ref "R9") (pin "1") (pinfunction "1_1") (pintype "passive"))
    )
    (net (code "76") (name "Net-(J3-Pad1)") (class "Default")
      (node (ref "J3") (pin "1") (pinfunction "1_1") (pintype "passive"))
      (node (ref "R15") (pin "1") (pinfunction "1_1") (pintype "passive"))
    )
    (net (code "77") (name "Net-(J4-Pad1)") (class "Default")
      (node (ref "J4") (pin "1") (pinfunction "1_1") (pintype "passive"))
      (node (ref "R10") (pin "1") (pinfunction "1_1") (pintype "passive"))
    )
    (net (code "78") (name "Net-(J5-Pad1)") (class "Default")
      (node (ref "J5") (pin "1") (pinfunction "1_1") (pintype "passive"))
      (node (ref "R11") (pin "1") (pinfunction "1_1") (pintype "passive"))
    )
    (net (code "79") (name "Net-(J6-Pad1)") (class "Default")
      (node (ref "J6") (pin "1") (pinfunction "1_1") (pintype "passive"))
      (node (ref "R16") (pin "2") (pinfunction "2_2") (pintype "passive"))
    )
    (net (code "80") (name "Net-(J7-CLK{slash}SCLK)") (class "Default")
      (node (ref "J7") (pin "5") (pinfunction "CLK/SCLK_5") (pintype "passive"))
      (node (ref "R58") (pin "1") (pinfunction "1_1") (pintype "passive"))
      (node (ref "R70") (pin "2") (pinfunction "2_2") (pintype "passive"))
      (node (ref "R75") (pin "2") (pinfunction "2_2") (pintype "passive"))
    )
    (net (code "81") (name "Net-(J7-CMD{slash}MOSI)") (class "Default")
      (node (ref "J7") (pin "3") (pinfunction "CMD/MOSI_3") (pintype "passive"))
      (node (ref "R56") (pin "1") (pinfunction "1_1") (pintype "passive"))
      (node (ref "R66") (pin "2") (pinfunction "2_2") (pintype "passive"))
      (node (ref "R73") (pin "2") (pinfunction "2_2") (pintype "passive"))
    )
    (net (code "82") (name "Net-(J7-DAT0{slash}MISO)") (class "Default")
      (node (ref "J7") (pin "7") (pinfunction "DAT0/MISO_7") (pintype "passive"))
      (node (ref "R57") (pin "1") (pinfunction "1_1") (pintype "passive"))
      (node (ref "R68") (pin "2") (pinfunction "2_2") (pintype "passive"))
      (node (ref "R74") (pin "2") (pinfunction "2_2") (pintype "passive"))
    )
    (net (code "83") (name "Net-(J7-DAT1{slash}RSV1)") (class "Default")
      (node (ref "J7") (pin "8") (pinfunction "DAT1/RSV1_8") (pintype "passive"))
      (node (ref "R61") (pin "1") (pinfunction "1_1") (pintype "passive"))
      (node (ref "R64") (pin "2") (pinfunction "2_2") (pintype "passive"))
    )
    (net (code "84") (name "Net-(J7-DAT2{slash}RSV)") (class "Default")
      (node (ref "J7") (pin "1") (pinfunction "DAT2/RSV_1") (pintype "passive"))
      (node (ref "R60") (pin "1") (pinfunction "1_1") (pintype "passive"))
      (node (ref "R63") (pin "2") (pinfunction "2_2") (pintype "passive"))
    )
    (net (code "85") (name "Net-(J7-DAT3{slash}CS)") (class "Default")
      (node (ref "J7") (pin "2") (pinfunction "DAT3/CS_2") (pintype "passive"))
      (node (ref "R59") (pin "1") (pinfunction "1_1") (pintype "passive"))
      (node (ref "R72") (pin "2") (pinfunction "2_2") (pintype "passive"))
      (node (ref "R76") (pin "2") (pinfunction "2_2") (pintype "passive"))
    )
    (net (code "86") (name "Net-(M1-HV1)") (class "Default")
      (node (ref "M1") (pin "12") (pinfunction "HV1_12") (pintype "passive"))
      (node (ref "R50") (pin "2") (pinfunction "2_2") (pintype "passive"))
    )
    (net (code "87") (name "Net-(M1-HV2)") (class "Default")
      (node (ref "M1") (pin "11") (pinfunction "HV2_11") (pintype "passive"))
      (node (ref "R52") (pin "2") (pinfunction "2_2") (pintype "passive"))
    )
    (net (code "88") (name "Net-(M1-HV3)") (class "Default")
      (node (ref "M1") (pin "8") (pinfunction "HV3_8") (pintype "passive"))
      (node (ref "R54") (pin "2") (pinfunction "2_2") (pintype "passive"))
    )
    (net (code "89") (name "Net-(M1-HV4)") (class "Default")
      (node (ref "M1") (pin "7") (pinfunction "HV4_7") (pintype "passive"))
      (node (ref "R55") (pin "2") (pinfunction "2_2") (pintype "passive"))
    )
    (net (code "90") (name "Net-(M1-LV1)") (class "Default")
      (node (ref "M1") (pin "1") (pinfunction "LV1_1") (pintype "passive"))
      (node (ref "R51") (pin "1") (pinfunction "1_1") (pintype "passive"))
    )
    (net (code "91") (name "Net-(M1-LV2)") (class "Default")
      (node (ref "M1") (pin "2") (pinfunction "LV2_2") (pintype "passive"))
      (node (ref "R53") (pin "1") (pinfunction "1_1") (pintype "passive"))
    )
    (net (code "92") (name "Net-(M1-LV3)") (class "Default")
      (node (ref "M1") (pin "5") (pinfunction "LV3_5") (pintype "passive"))
      (node (ref "R63") (pin "1") (pinfunction "1_1") (pintype "passive"))
    )
    (net (code "93") (name "Net-(M1-LV4)") (class "Default")
      (node (ref "M1") (pin "6") (pinfunction "LV4_6") (pintype "passive"))
      (node (ref "R64") (pin "1") (pinfunction "1_1") (pintype "passive"))
    )
    (net (code "94") (name "Net-(M2-HV1)") (class "Default")
      (node (ref "M2") (pin "12") (pinfunction "HV1_12") (pintype "passive"))
      (node (ref "R65") (pin "2") (pinfunction "2_2") (pintype "passive"))
    )
    (net (code "95") (name "Net-(M2-HV2)") (class "Default")
      (node (ref "M2") (pin "11") (pinfunction "HV2_11") (pintype "passive"))
      (node (ref "R67") (pin "2") (pinfunction "2_2") (pintype "passive"))
    )
    (net (code "96") (name "Net-(M2-HV3)") (class "Default")
      (node (ref "M2") (pin "8") (pinfunction "HV3_8") (pintype "passive"))
      (node (ref "R69") (pin "2") (pinfunction "2_2") (pintype "passive"))
    )
    (net (code "97") (name "Net-(M2-HV4)") (class "Default")
      (node (ref "M2") (pin "7") (pinfunction "HV4_7") (pintype "passive"))
      (node (ref "R71") (pin "2") (pinfunction "2_2") (pintype "passive"))
    )
    (net (code "98") (name "Net-(M2-LV1)") (class "Default")
      (node (ref "M2") (pin "1") (pinfunction "LV1_1") (pintype "passive"))
      (node (ref "R66") (pin "1") (pinfunction "1_1") (pintype "passive"))
      (node (ref "R73") (pin "1") (pinfunction "1_1") (pintype "passive"))
    )
    (net (code "99") (name "Net-(M2-LV2)") (class "Default")
      (node (ref "M2") (pin "2") (pinfunction "LV2_2") (pintype "passive"))
      (node (ref "R68") (pin "1") (pinfunction "1_1") (pintype "passive"))
      (node (ref "R74") (pin "1") (pinfunction "1_1") (pintype "passive"))
    )
    (net (code "100") (name "Net-(M2-LV3)") (class "Default")
      (node (ref "M2") (pin "5") (pinfunction "LV3_5") (pintype "passive"))
      (node (ref "R70") (pin "1") (pinfunction "1_1") (pintype "passive"))
      (node (ref "R75") (pin "1") (pinfunction "1_1") (pintype "passive"))
    )
    (net (code "101") (name "Net-(M2-LV4)") (class "Default")
      (node (ref "M2") (pin "6") (pinfunction "LV4_6") (pintype "passive"))
      (node (ref "R72") (pin "1") (pinfunction "1_1") (pintype "passive"))
      (node (ref "R76") (pin "1") (pinfunction "1_1") (pintype "passive"))
    )
    (net (code "102") (name "Net-(R2-Pad1)") (class "Default")
      (node (ref "R2") (pin "1") (pinfunction "1_1") (pintype "passive"))
      (node (ref "TP1") (pin "1") (pinfunction "1_1") (pintype "passive"))
    )
    (net (code "103") (name "Net-(R3-Pad2)") (class "Default")
      (node (ref "R3") (pin "2") (pinfunction "2_2") (pintype "passive"))
      (node (ref "TP2") (pin "1") (pinfunction "1_1") (pintype "passive"))
    )
    (net (code "104") (name "Net-(R5-Pad1)") (class "Default")
      (node (ref "R5") (pin "1") (pinfunction "1_1") (pintype "passive"))
      (node (ref "TP3") (pin "1") (pinfunction "1_1") (pintype "passive"))
    )
    (net (code "105") (name "Net-(R50-Pad1)") (class "Default")
      (node (ref "R50") (pin "1") (pinfunction "1_1") (pintype "passive"))
      (node (ref "TP4") (pin "1") (pinfunction "1_1") (pintype "passive"))
    )
    (net (code "106") (name "Net-(R51-Pad2)") (class "Default")
      (node (ref "R51") (pin "2") (pinfunction "2_2") (pintype "passive"))
      (node (ref "TP5") (pin "1") (pinfunction "1_1") (pintype "passive"))
    )
    (net (code "107") (name "Net-(R52-Pad1)") (class "Default")
      (node (ref "R52") (pin "1") (pinfunction "1_1") (pintype "passive"))
      (node (ref "TP6") (pin "1") (pinfunction "1_1") (pintype "passive"))
    )
    (net (code "108") (name "Net-(R53-Pad2)") (class "Default")
      (node (ref "R53") (pin "2") (pinfunction "2_2") (pintype "passive"))
      (node (ref "TP7") (pin "1") (pinfunction "1_1") (pintype "passive"))
    )
  )
)
